# SSTuino_Evo.net
KiCad netlist of a schematic drawn in EAGLE
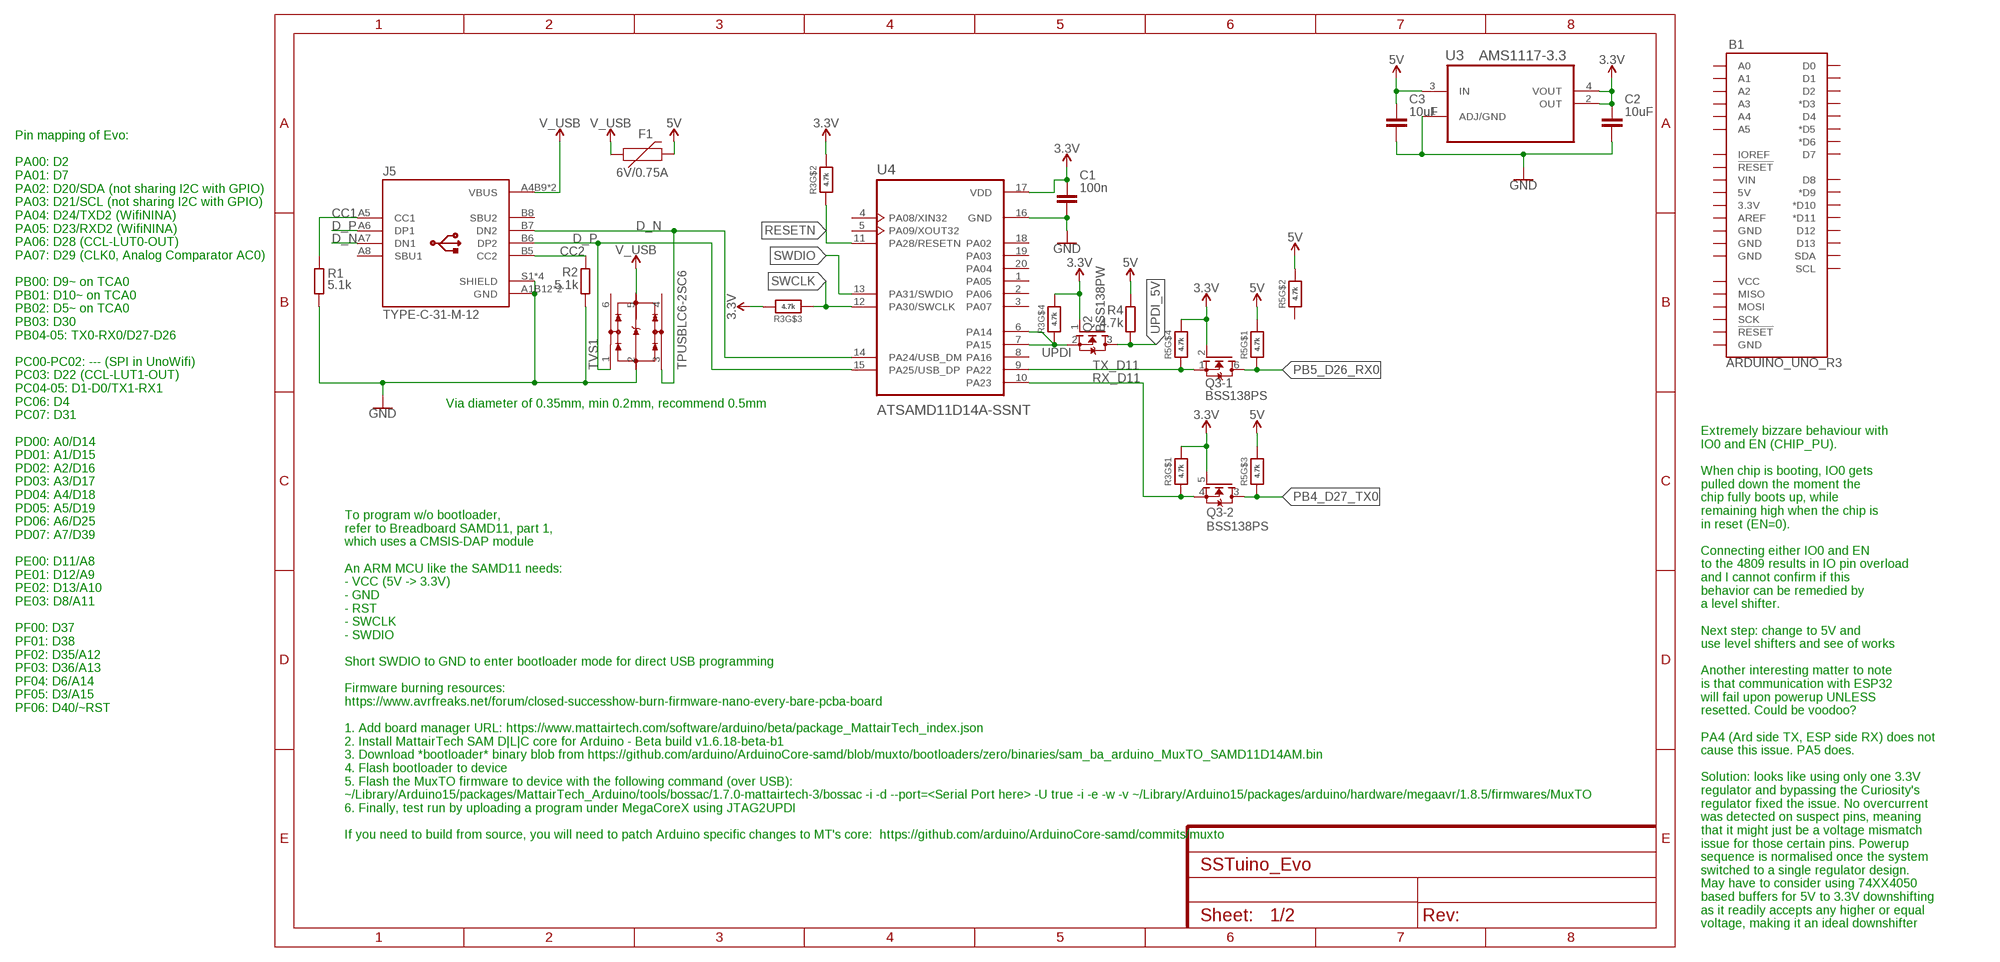
[diagram p0: schematic, sheet 1]
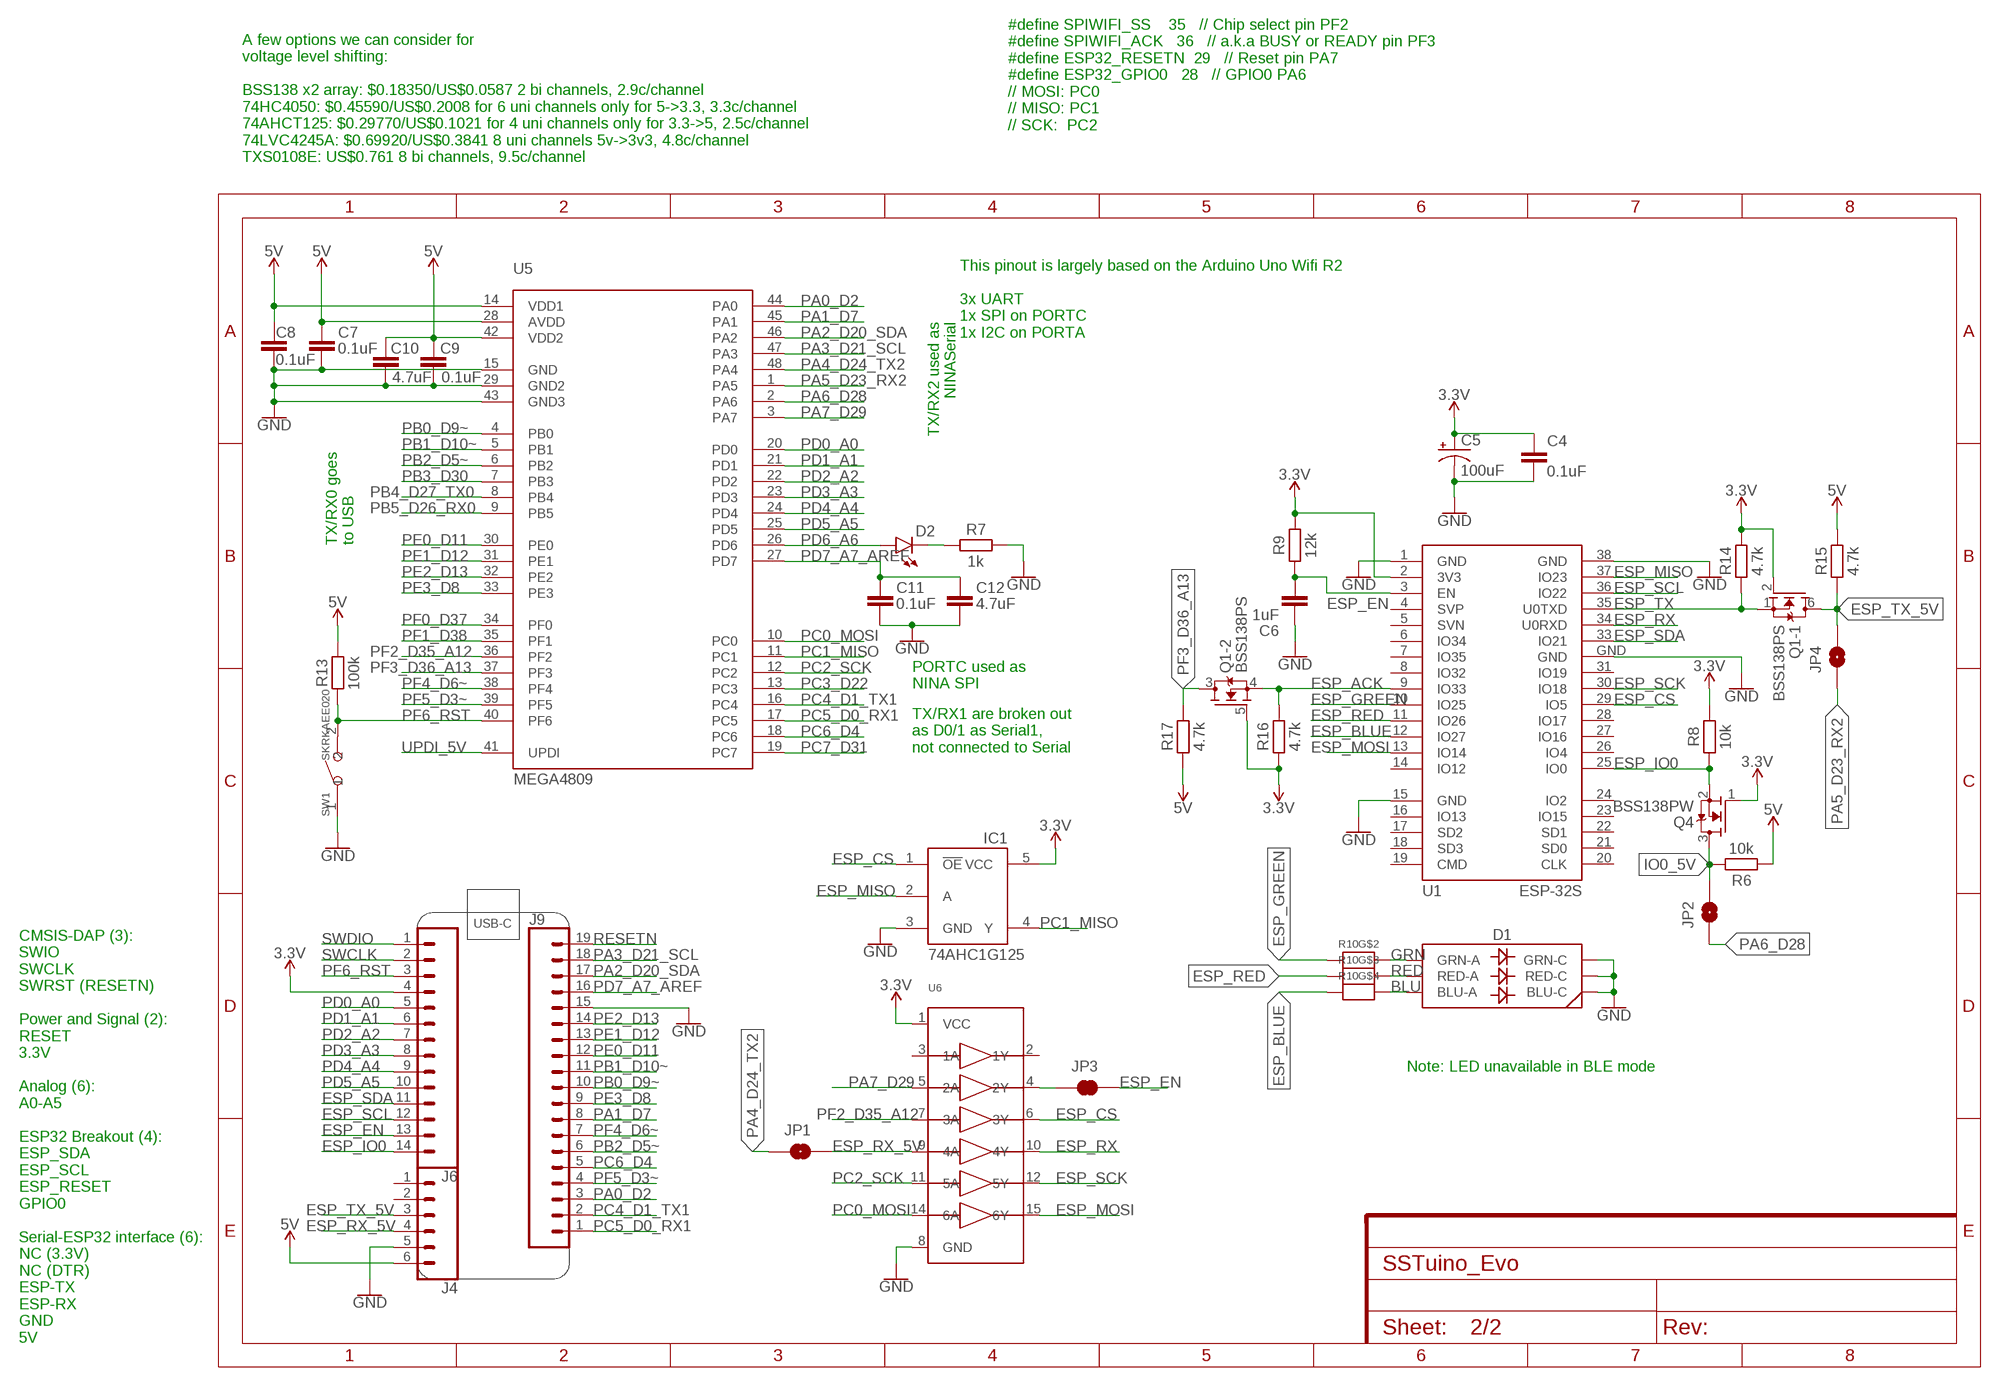
[diagram p1: schematic, sheet 2]

(export (version "E")
  (design (tool "Eeschema 10.0.6"))
  (components
    (comp (ref "C4")
      (value "0.1uF")
      (footprint "eagle-import:CAPC1005X60")
      (libsource (lib "eagle-import") (part "CCHIP-0402(1005-METRIC)_"))
    )
    (comp (ref "C5")
      (value "100uF")
      (footprint "eagle-import:CAPMP3216X180N")
      (libsource (lib "eagle-import") (part "C-POL-USTANTALUM-1206(3216-METRIC)_"))
    )
    (comp (ref "C6")
      (value "1uF")
      (footprint "eagle-import:CAPC1005X60")
      (libsource (lib "eagle-import") (part "CCHIP-0402(1005-METRIC)_"))
    )
    (comp (ref "C7")
      (value "0.1uF")
      (footprint "eagle-import:CAPC1005X60")
      (libsource (lib "eagle-import") (part "CCHIP-0402(1005-METRIC)_"))
    )
    (comp (ref "C8")
      (value "0.1uF")
      (footprint "eagle-import:CAPC1005X60")
      (libsource (lib "eagle-import") (part "CCHIP-0402(1005-METRIC)_"))
    )
    (comp (ref "C9")
      (value "0.1uF")
      (footprint "eagle-import:CAPC1005X60")
      (libsource (lib "eagle-import") (part "CCHIP-0402(1005-METRIC)_"))
    )
    (comp (ref "C10")
      (value "4.7uF")
      (footprint "eagle-import:CAPC1005X60")
      (libsource (lib "eagle-import") (part "CCHIP-0402(1005-METRIC)_"))
    )
    (comp (ref "C11")
      (value "0.1uF")
      (footprint "eagle-import:CAPC1005X60")
      (libsource (lib "eagle-import") (part "CCHIP-0402(1005-METRIC)_"))
    )
    (comp (ref "C12")
      (value "4.7uF")
      (footprint "eagle-import:CAPC1005X60")
      (libsource (lib "eagle-import") (part "CCHIP-0402(1005-METRIC)_"))
    )
    (comp (ref "D1")
      (value "LED-RGBTC5050RGBF08")
      (footprint "eagle-import:LED-TRICOLOR-5050")
      (libsource (lib "eagle-import") (part "LED-RGBTC5050RGBF08"))
    )
    (comp (ref "D2")
      (value "LED0603")
      (footprint "eagle-import:LED-0603")
      (libsource (lib "eagle-import") (part "LED0603"))
    )
    (comp (ref "IC1")
      (value "74AHC1G125")
      (footprint "eagle-import:SOT23-5L")
      (fields (field (name "LCSC_PART") "C124295"))
      (libsource (lib "eagle-import") (part "74AHC1G125"))
    )
    (comp (ref "J4")
      (value "CONN_06NO_SILK_FEMALE_PTH")
      (footprint "eagle-import:1X06_NO_SILK")
      (libsource (lib "eagle-import") (part "CONN_06NO_SILK_FEMALE_PTH"))
    )
    (comp (ref "J6")
      (value "CONN_14NO_SILK")
      (footprint "eagle-import:1X14_NO_SILK")
      (libsource (lib "eagle-import") (part "CONN_14NO_SILK"))
    )
    (comp (ref "J9")
      (value "CONN_191X19_NO_SILK")
      (footprint "eagle-import:1X19_NO_SILK")
      (libsource (lib "eagle-import") (part "CONN_191X19_NO_SILK"))
    )
    (comp (ref "JP1")
      (value "JUMPER-SMT_2_NO_SILK")
      (footprint "eagle-import:SMT-JUMPER_2_NO_SILK")
      (libsource (lib "eagle-import") (part "JUMPER-SMT_2_NO_SILK"))
    )
    (comp (ref "JP2")
      (value "JUMPER-SMT_2_NO_SILK")
      (footprint "eagle-import:SMT-JUMPER_2_NO_SILK")
      (libsource (lib "eagle-import") (part "JUMPER-SMT_2_NO_SILK"))
    )
    (comp (ref "JP3")
      (value "JUMPER-SMT_2_NC_TRACE_SILK")
      (footprint "eagle-import:SMT-JUMPER_2_NC_TRACE_SILK")
      (libsource (lib "eagle-import") (part "JUMPER-SMT_2_NC_TRACE_SILK"))
    )
    (comp (ref "JP4")
      (value "JUMPER-SMT_2_NO_SILK")
      (footprint "eagle-import:SMT-JUMPER_2_NO_SILK")
      (libsource (lib "eagle-import") (part "JUMPER-SMT_2_NO_SILK"))
    )
    (comp (ref "Q1")
      (value "BSS138PS")
      (footprint "eagle-import:ARDUINO-TRANSISTORS_SOT363")
      (fields (field (name "MANUFACTURER") "NXP") (field (name "LCSC_PART") "C193381"))
      (libsource (lib "eagle-import") (part "BSS138PS"))
    )
    (comp (ref "Q4")
      (value "BSS138PW")
      (footprint "eagle-import:SOT65P210X110-3N")
      (fields (field (name "MF") "NXP Semiconductors"))
      (libsource (lib "eagle-import") (part "BSS138PW"))
    )
    (comp (ref "R6")
      (value "10k")
      (footprint "eagle-import:RESC1005X40")
      (libsource (lib "eagle-import") (part "RCHIP-0402(1005-METRIC)_"))
    )
    (comp (ref "R7")
      (value "1k")
      (footprint "eagle-import:RESC1005X40")
      (libsource (lib "eagle-import") (part "RCHIP-0402(1005-METRIC)_"))
    )
    (comp (ref "R8")
      (value "10k")
      (footprint "eagle-import:RESC1005X40")
      (libsource (lib "eagle-import") (part "RCHIP-0402(1005-METRIC)_"))
    )
    (comp (ref "R9")
      (value "12k")
      (footprint "eagle-import:RESC1005X40")
      (libsource (lib "eagle-import") (part "RCHIP-0402(1005-METRIC)_"))
    )
    (comp (ref "R10")
      (value "RESISTOR_4PACK0402")
      (footprint "eagle-import:RESPACK_4X0402")
      (libsource (lib "eagle-import") (part "RESISTOR_4PACK0402"))
    )
    (comp (ref "R13")
      (value "100k")
      (footprint "eagle-import:RESC1005X40")
      (libsource (lib "eagle-import") (part "RCHIP-0402(1005-METRIC)_"))
    )
    (comp (ref "R14")
      (value "4.7k")
      (footprint "eagle-import:RESC1005X40")
      (libsource (lib "eagle-import") (part "RCHIP-0402(1005-METRIC)_"))
    )
    (comp (ref "R15")
      (value "4.7k")
      (footprint "eagle-import:RESC1005X40")
      (libsource (lib "eagle-import") (part "RCHIP-0402(1005-METRIC)_"))
    )
    (comp (ref "R16")
      (value "4.7k")
      (footprint "eagle-import:RESC1005X40")
      (libsource (lib "eagle-import") (part "RCHIP-0402(1005-METRIC)_"))
    )
    (comp (ref "R17")
      (value "4.7k")
      (footprint "eagle-import:RESC1005X40")
      (libsource (lib "eagle-import") (part "RCHIP-0402(1005-METRIC)_"))
    )
    (comp (ref "SW1")
      (value "SKRKAEE020")
      (footprint "eagle-import:SW2-2.6-3.9X2.9X1.5+0.4MM")
      (fields (field (name "LCSC_PART") "C115357") (field (name "LCSC_PART_1") "C115357"))
      (libsource (lib "eagle-import") (part "SMD-BUTTON(2P-3.9X2.9X1.5+0.4MM)-SKRKAEE020"))
    )
    (comp (ref "U1")
      (value "ESP-32S")
      (footprint "eagle-import:ESP-32S")
      (libsource (lib "eagle-import") (part "ESP-32S"))
    )
    (comp (ref "U5")
      (value "MEGA4809")
      (footprint "eagle-import:TQFP48")
      (fields (field (name "LCSC_PART") "C189475"))
      (libsource (lib "eagle-import") (part "MEGA4809"))
    )
    (comp (ref "U6")
      (value "74HC4050DTSSOP")
      (footprint "eagle-import:TSSOP16")
      (fields (field (name "LCSC_PART") "C352825"))
      (libsource (lib "eagle-import") (part "74HC4050DTSSOP"))
    )
    (comp (ref "B1")
      (value "ARDUINO_UNO_R3")
      (footprint "eagle-import:ARDUINO_R3")
      (libsource (lib "eagle-import") (part "ARDUINO_UNO_R3"))
    )
    (comp (ref "C1")
      (value "100n")
      (footprint "eagle-import:CAPC1005X60")
      (libsource (lib "eagle-import") (part "CCHIP-0402(1005-METRIC)_"))
    )
    (comp (ref "C2")
      (value "10uF")
      (footprint "eagle-import:CAPC1608X85")
      (libsource (lib "eagle-import") (part "CCHIP-0603(1608-METRIC)_"))
    )
    (comp (ref "C3")
      (value "10uF")
      (footprint "eagle-import:CAPC1608X85")
      (libsource (lib "eagle-import") (part "CCHIP-0603(1608-METRIC)_"))
    )
    (comp (ref "F1")
      (value "6V/0.75A")
      (footprint "eagle-import:1206")
      (fields (field (name "LCSC_PART") "C99563"))
      (libsource (lib "eagle-import") (part "PPTC_THREE-QUARTER-AMP"))
    )
    (comp (ref "J5")
      (value "TYPE-C-31-M-12")
      (footprint "eagle-import:HRO_TYPE-C-31-M-12")
      (fields (field (name "MF") "HRO Electronics Co., Ltd.") (field (name "LCSC_PART") "C165948"))
      (libsource (lib "eagle-import") (part "TYPE-C-31-M-12"))
    )
    (comp (ref "Q2")
      (value "BSS138PW")
      (footprint "eagle-import:SOT65P210X110-3N")
      (fields (field (name "MF") "NXP Semiconductors"))
      (libsource (lib "eagle-import") (part "BSS138PW"))
    )
    (comp (ref "Q3")
      (value "BSS138PS")
      (footprint "eagle-import:ARDUINO-TRANSISTORS_SOT363")
      (fields (field (name "MANUFACTURER") "NXP") (field (name "LCSC_PART") "C193381"))
      (libsource (lib "eagle-import") (part "BSS138PS"))
    )
    (comp (ref "R1")
      (value "5.1k")
      (footprint "eagle-import:RESC1005X40")
      (libsource (lib "eagle-import") (part "RCHIP-0402(1005-METRIC)_"))
    )
    (comp (ref "R2")
      (value "5.1k")
      (footprint "eagle-import:RESC1005X40")
      (libsource (lib "eagle-import") (part "RCHIP-0402(1005-METRIC)_"))
    )
    (comp (ref "R3")
      (value "4.7k")
      (footprint "eagle-import:RESPACK_4X0402")
      (fields (field (name "LCSC_PART") "C1980"))
      (libsource (lib "eagle-import") (part "RESISTOR_4PACK0402"))
    )
    (comp (ref "R4")
      (value "4.7k")
      (footprint "eagle-import:RESC1005X40")
      (libsource (lib "eagle-import") (part "RCHIP-0402(1005-METRIC)_"))
    )
    (comp (ref "R5")
      (value "4.7k")
      (footprint "eagle-import:RESPACK_4X0402")
      (fields (field (name "LCSC_PART") "C1980"))
      (libsource (lib "eagle-import") (part "RESISTOR_4PACK0402"))
    )
    (comp (ref "TVS1")
      (value "TPUSBLC6-2SC6")
      (footprint "eagle-import:SOT95P280X110-6N")
      (fields (field (name "LCSC_PART") "C558442"))
      (libsource (lib "eagle-import") (part "TPUSBLC6-2SC6"))
    )
    (comp (ref "U3")
      (value "AMS1117-3.3")
      (footprint "eagle-import:SOT230P696X180-4N")
      (fields (field (name "MPN") "LM1117MP-3.3") (field (name "LCSC_PART") "C6186"))
      (libsource (lib "eagle-import") (part "LM1117MP-3.3"))
    )
    (comp (ref "U4")
      (value "ATSAMD11D14A-SSNT")
      (footprint "eagle-import:SOIC127P1030X265-20N")
      (fields (field (name "MF") "Microchip") (field (name "LCSC_PART") "C2053599"))
      (libsource (lib "eagle-import") (part "ATSAMD11D14A-SSNT"))
    )
  )
  (nets
    (net (code "1") (name "3.3V") (class "Default")
      (node (ref "C1") (pin "1") (pinfunction "1_1") (pintype "passive"))
      (node (ref "C2") (pin "1") (pinfunction "1_1") (pintype "passive"))
      (node (ref "C4") (pin "1") (pinfunction "1_1") (pintype "passive"))
      (node (ref "C5") (pin "1") (pinfunction "+_1") (pintype "passive"))
      (node (ref "IC1") (pin "5") (pinfunction "VCC_5") (pintype "power_in"))
      (node (ref "J6") (pin "4") (pinfunction "4_4") (pintype "passive"))
      (node (ref "Q1") (pin "2") (pinfunction "G_2") (pintype "passive"))
      (node (ref "Q1") (pin "5") (pinfunction "G_5") (pintype "passive"))
      (node (ref "Q2") (pin "1") (pinfunction "G_1") (pintype "passive"))
      (node (ref "Q3") (pin "2") (pinfunction "G_2") (pintype "passive"))
      (node (ref "Q3") (pin "5") (pinfunction "G_5") (pintype "passive"))
      (node (ref "Q4") (pin "1") (pinfunction "G_1") (pintype "passive"))
      (node (ref "R14") (pin "2") (pinfunction "2_2") (pintype "passive"))
      (node (ref "R16") (pin "1") (pinfunction "1_1") (pintype "passive"))
      (node (ref "R3") (pin "5") (pinfunction "2_5") (pintype "passive"))
      (node (ref "R3") (pin "6") (pinfunction "2_6") (pintype "passive"))
      (node (ref "R3") (pin "7") (pinfunction "2_7") (pintype "passive"))
      (node (ref "R3") (pin "8") (pinfunction "2_8") (pintype "passive"))
      (node (ref "R5") (pin "5") (pinfunction "2_5") (pintype "passive"))
      (node (ref "R8") (pin "2") (pinfunction "2_2") (pintype "passive"))
      (node (ref "R9") (pin "2") (pinfunction "2_2") (pintype "passive"))
      (node (ref "U1") (pin "2") (pinfunction "3V3_2") (pintype "power_in"))
      (node (ref "U3") (pin "2") (pinfunction "OUT_2") (pintype "output"))
      (node (ref "U3") (pin "4") (pinfunction "VOUT_4") (pintype "output"))
      (node (ref "U4") (pin "17") (pinfunction "VDD_17") (pintype "power_in"))
      (node (ref "U6") (pin "1") (pinfunction "VCC_1") (pintype "bidirectional"))
    )
    (net (code "2") (name "5V") (class "Default")
      (node (ref "C10") (pin "1") (pinfunction "1_1") (pintype "passive"))
      (node (ref "C3") (pin "1") (pinfunction "1_1") (pintype "passive"))
      (node (ref "C7") (pin "1") (pinfunction "1_1") (pintype "passive"))
      (node (ref "C8") (pin "1") (pinfunction "1_1") (pintype "passive"))
      (node (ref "C9") (pin "1") (pinfunction "1_1") (pintype "passive"))
      (node (ref "F1") (pin "2") (pinfunction "2_2") (pintype "bidirectional"))
      (node (ref "J4") (pin "6") (pinfunction "6_6") (pintype "passive"))
      (node (ref "R13") (pin "2") (pinfunction "2_2") (pintype "passive"))
      (node (ref "R15") (pin "2") (pinfunction "2_2") (pintype "passive"))
      (node (ref "R17") (pin "1") (pinfunction "1_1") (pintype "passive"))
      (node (ref "R4") (pin "2") (pinfunction "2_2") (pintype "passive"))
      (node (ref "R5") (pin "6") (pinfunction "2_6") (pintype "passive"))
      (node (ref "R5") (pin "7") (pinfunction "2_7") (pintype "passive"))
      (node (ref "R5") (pin "8") (pinfunction "2_8") (pintype "passive"))
      (node (ref "R6") (pin "1") (pinfunction "1_1") (pintype "passive"))
      (node (ref "U3") (pin "3") (pinfunction "IN_3") (pintype "input"))
      (node (ref "U5") (pin "14") (pinfunction "VDD1_14") (pintype "bidirectional"))
      (node (ref "U5") (pin "28") (pinfunction "AVDD_28") (pintype "bidirectional"))
      (node (ref "U5") (pin "42") (pinfunction "VDD2_42") (pintype "bidirectional"))
    )
    (net (code "3") (name "BLU") (class "Default")
      (node (ref "D1") (pin "6") (pinfunction "BLU-A_6") (pintype "bidirectional"))
      (node (ref "R10") (pin "5") (pinfunction "2_5") (pintype "passive"))
    )
    (net (code "4") (name "CC1") (class "Default")
      (node (ref "J5") (pin "A5") (pinfunction "CC1_A5") (pintype "bidirectional"))
      (node (ref "R1") (pin "1") (pinfunction "1_1") (pintype "passive"))
    )
    (net (code "5") (name "CC2") (class "Default")
      (node (ref "J5") (pin "B5") (pinfunction "CC2_B5") (pintype "bidirectional"))
      (node (ref "R2") (pin "2") (pinfunction "2_2") (pintype "passive"))
    )
    (net (code "6") (name "D_N") (class "Default")
      (node (ref "J5") (pin "A7") (pinfunction "DN1_A7") (pintype "bidirectional"))
      (node (ref "J5") (pin "B7") (pinfunction "DN2_B7") (pintype "bidirectional"))
      (node (ref "TVS1") (pin "3") (pinfunction "IO2_3") (pintype "passive"))
      (node (ref "U4") (pin "14") (pinfunction "PA24/USB_DM_14") (pintype "bidirectional"))
    )
    (net (code "7") (name "D_P") (class "Default")
      (node (ref "J5") (pin "A6") (pinfunction "DP1_A6") (pintype "bidirectional"))
      (node (ref "J5") (pin "B6") (pinfunction "DP2_B6") (pintype "bidirectional"))
      (node (ref "TVS1") (pin "1") (pinfunction "IO1_1") (pintype "passive"))
      (node (ref "U4") (pin "15") (pinfunction "PA25/USB_DP_15") (pintype "bidirectional"))
    )
    (net (code "8") (name "ESP_ACK") (class "Default")
      (node (ref "Q1") (pin "4") (pinfunction "S_4") (pintype "passive"))
      (node (ref "R16") (pin "2") (pinfunction "2_2") (pintype "passive"))
      (node (ref "U1") (pin "9") (pinfunction "IO33_9") (pintype "bidirectional"))
    )
    (net (code "9") (name "ESP_BLUE") (class "Default")
      (node (ref "R10") (pin "4") (pinfunction "1_4") (pintype "passive"))
      (node (ref "U1") (pin "12") (pinfunction "IO27_12") (pintype "bidirectional"))
    )
    (net (code "10") (name "ESP_CS") (class "Default")
      (node (ref "IC1") (pin "1") (pinfunction "~{OE}_1") (pintype "input"))
      (node (ref "U1") (pin "29") (pinfunction "IO5_29") (pintype "bidirectional"))
      (node (ref "U6") (pin "6") (pinfunction "3Y_6") (pintype "bidirectional"))
    )
    (net (code "11") (name "ESP_EN") (class "Default")
      (node (ref "C6") (pin "2") (pinfunction "2_2") (pintype "passive"))
      (node (ref "J6") (pin "13") (pinfunction "13_13") (pintype "passive"))
      (node (ref "JP3") (pin "2") (pinfunction "2_2") (pintype "passive"))
      (node (ref "R9") (pin "1") (pinfunction "1_1") (pintype "passive"))
      (node (ref "U1") (pin "3") (pinfunction "EN_3") (pintype "input"))
    )
    (net (code "12") (name "ESP_GREEN") (class "Default")
      (node (ref "R10") (pin "2") (pinfunction "1_2") (pintype "passive"))
      (node (ref "U1") (pin "10") (pinfunction "IO25_10") (pintype "bidirectional"))
    )
    (net (code "13") (name "ESP_IO0") (class "Default")
      (node (ref "J6") (pin "14") (pinfunction "14_14") (pintype "passive"))
      (node (ref "Q4") (pin "2") (pinfunction "S_2") (pintype "passive"))
      (node (ref "R8") (pin "1") (pinfunction "1_1") (pintype "passive"))
      (node (ref "U1") (pin "25") (pinfunction "IO0_25") (pintype "bidirectional"))
    )
    (net (code "14") (name "ESP_MISO") (class "Default")
      (node (ref "IC1") (pin "2") (pinfunction "A_2") (pintype "input"))
      (node (ref "U1") (pin "37") (pinfunction "IO23_37") (pintype "bidirectional"))
    )
    (net (code "15") (name "ESP_MOSI") (class "Default")
      (node (ref "U1") (pin "13") (pinfunction "IO14_13") (pintype "bidirectional"))
      (node (ref "U6") (pin "15") (pinfunction "6Y_15") (pintype "bidirectional"))
    )
    (net (code "16") (name "ESP_RED") (class "Default")
      (node (ref "R10") (pin "3") (pinfunction "1_3") (pintype "passive"))
      (node (ref "U1") (pin "11") (pinfunction "IO26_11") (pintype "bidirectional"))
    )
    (net (code "17") (name "ESP_RX") (class "Default")
      (node (ref "U1") (pin "34") (pinfunction "U0RXD_34") (pintype "bidirectional"))
      (node (ref "U6") (pin "10") (pinfunction "4Y_10") (pintype "bidirectional"))
    )
    (net (code "18") (name "ESP_RX_5V") (class "Default")
      (node (ref "J4") (pin "4") (pinfunction "4_4") (pintype "passive"))
      (node (ref "JP1") (pin "2") (pinfunction "2_2") (pintype "passive"))
      (node (ref "U6") (pin "9") (pinfunction "4A_9") (pintype "bidirectional"))
    )
    (net (code "19") (name "ESP_SCK") (class "Default")
      (node (ref "U1") (pin "30") (pinfunction "IO18_30") (pintype "bidirectional"))
      (node (ref "U6") (pin "12") (pinfunction "5Y_12") (pintype "bidirectional"))
    )
    (net (code "20") (name "ESP_SCL") (class "Default")
      (node (ref "J6") (pin "12") (pinfunction "12_12") (pintype "passive"))
      (node (ref "U1") (pin "36") (pinfunction "IO22_36") (pintype "bidirectional"))
    )
    (net (code "21") (name "ESP_SDA") (class "Default")
      (node (ref "J6") (pin "11") (pinfunction "11_11") (pintype "passive"))
      (node (ref "U1") (pin "33") (pinfunction "IO21_33") (pintype "bidirectional"))
    )
    (net (code "22") (name "ESP_TX") (class "Default")
      (node (ref "Q1") (pin "1") (pinfunction "S_1") (pintype "passive"))
      (node (ref "R14") (pin "1") (pinfunction "1_1") (pintype "passive"))
      (node (ref "U1") (pin "35") (pinfunction "U0TXD_35") (pintype "bidirectional"))
    )
    (net (code "23") (name "ESP_TX_5V") (class "Default")
      (node (ref "J4") (pin "3") (pinfunction "3_3") (pintype "passive"))
      (node (ref "JP4") (pin "2") (pinfunction "2_2") (pintype "passive"))
      (node (ref "Q1") (pin "6") (pinfunction "D_6") (pintype "passive"))
      (node (ref "R15") (pin "1") (pinfunction "1_1") (pintype "passive"))
    )
    (net (code "24") (name "GND") (class "Default")
      (node (ref "C1") (pin "2") (pinfunction "2_2") (pintype "passive"))
      (node (ref "C10") (pin "2") (pinfunction "2_2") (pintype "passive"))
      (node (ref "C11") (pin "2") (pinfunction "2_2") (pintype "passive"))
      (node (ref "C12") (pin "2") (pinfunction "2_2") (pintype "passive"))
      (node (ref "C2") (pin "2") (pinfunction "2_2") (pintype "passive"))
      (node (ref "C3") (pin "2") (pinfunction "2_2") (pintype "passive"))
      (node (ref "C4") (pin "2") (pinfunction "2_2") (pintype "passive"))
      (node (ref "C5") (pin "2") (pinfunction "-_2") (pintype "passive"))
      (node (ref "C6") (pin "1") (pinfunction "1_1") (pintype "passive"))
      (node (ref "C7") (pin "2") (pinfunction "2_2") (pintype "passive"))
      (node (ref "C8") (pin "2") (pinfunction "2_2") (pintype "passive"))
      (node (ref "C9") (pin "2") (pinfunction "2_2") (pintype "passive"))
      (node (ref "D1") (pin "1") (pinfunction "BLU-C_1") (pintype "bidirectional"))
      (node (ref "D1") (pin "2") (pinfunction "RED-C_2") (pintype "bidirectional"))
      (node (ref "D1") (pin "3") (pinfunction "GRN-C_3") (pintype "bidirectional"))
      (node (ref "IC1") (pin "3") (pinfunction "GND_3") (pintype "power_in"))
      (node (ref "J4") (pin "5") (pinfunction "5_5") (pintype "passive"))
      (node (ref "J5") (pin "A1B12") (pinfunction "GND_A1B12") (pintype "power_in"))
      (node (ref "J5") (pin "B1A12") (pinfunction "GND_B1A12") (pintype "power_in"))
      (node (ref "J5") (pin "S1") (pinfunction "SHIELD_S1") (pintype "passive"))
      (node (ref "J5") (pin "S2") (pinfunction "SHIELD_S2") (pintype "passive"))
      (node (ref "J5") (pin "S3") (pinfunction "SHIELD_S3") (pintype "passive"))
      (node (ref "J5") (pin "S4") (pinfunction "SHIELD_S4") (pintype "passive"))
      (node (ref "J9") (pin "15") (pinfunction "15_15") (pintype "passive"))
      (node (ref "R1") (pin "2") (pinfunction "2_2") (pintype "passive"))
      (node (ref "R2") (pin "1") (pinfunction "1_1") (pintype "passive"))
      (node (ref "R7") (pin "2") (pinfunction "2_2") (pintype "passive"))
      (node (ref "SW1") (pin "1") (pinfunction "1_1") (pintype "bidirectional"))
      (node (ref "TVS1") (pin "2") (pinfunction "VSS_2") (pintype "power_in"))
      (node (ref "U1") (pin "1") (pinfunction "GND_1") (pintype "power_in"))
      (node (ref "U1") (pin "15") (pinfunction "GND_15") (pintype "power_in"))
      (node (ref "U1") (pin "38") (pinfunction "GND_38") (pintype "power_in"))
      (node (ref "U1") (pin "GND") (pinfunction "GND_GND") (pintype "power_in"))
      (node (ref "U3") (pin "1") (pinfunction "ADJ/GND_1") (pintype "passive"))
      (node (ref "U4") (pin "16") (pinfunction "GND_16") (pintype "power_in"))
      (node (ref "U5") (pin "15") (pinfunction "GND_15") (pintype "bidirectional"))
      (node (ref "U5") (pin "29") (pinfunction "GND2_29") (pintype "bidirectional"))
      (node (ref "U5") (pin "43") (pinfunction "GND3_43") (pintype "bidirectional"))
      (node (ref "U6") (pin "8") (pinfunction "GND_8") (pintype "bidirectional"))
    )
    (net (code "25") (name "GRN") (class "Default")
      (node (ref "D1") (pin "4") (pinfunction "GRN-A_4") (pintype "bidirectional"))
      (node (ref "R10") (pin "7") (pinfunction "2_7") (pintype "passive"))
    )
    (net (code "26") (name "IO0_5V") (class "Default")
      (node (ref "JP2") (pin "2") (pinfunction "2_2") (pintype "passive"))
      (node (ref "Q4") (pin "3") (pinfunction "D_3") (pintype "passive"))
      (node (ref "R6") (pin "2") (pinfunction "2_2") (pintype "passive"))
    )
    (net (code "27") (name "Net-(D2-PadC)") (class "Default")
      (node (ref "D2") (pin "C") (pinfunction "C_C") (pintype "passive"))
      (node (ref "R7") (pin "1") (pinfunction "1_1") (pintype "passive"))
    )
    (net (code "28") (name "Net-(U6-2Y)") (class "Default")
      (node (ref "JP3") (pin "1") (pinfunction "1_1") (pintype "passive"))
      (node (ref "U6") (pin "4") (pinfunction "2Y_4") (pintype "bidirectional"))
    )
    (net (code "29") (name "PA0_D2") (class "Default")
      (node (ref "J9") (pin "3") (pinfunction "3_3") (pintype "passive"))
      (node (ref "U5") (pin "44") (pinfunction "PA0_44") (pintype "bidirectional"))
    )
    (net (code "30") (name "PA1_D7") (class "Default")
      (node (ref "J9") (pin "8") (pinfunction "8_8") (pintype "passive"))
      (node (ref "U5") (pin "45") (pinfunction "PA1_45") (pintype "bidirectional"))
    )
    (net (code "31") (name "PA2_D20_SDA") (class "Default")
      (node (ref "J9") (pin "17") (pinfunction "17_17") (pintype "passive"))
      (node (ref "U5") (pin "46") (pinfunction "PA2_46") (pintype "bidirectional"))
    )
    (net (code "32") (name "PA3_D21_SCL") (class "Default")
      (node (ref "J9") (pin "18") (pinfunction "18_18") (pintype "passive"))
      (node (ref "U5") (pin "47") (pinfunction "PA3_47") (pintype "bidirectional"))
    )
    (net (code "33") (name "PA4_D24_TX2") (class "Default")
      (node (ref "JP1") (pin "1") (pinfunction "1_1") (pintype "passive"))
      (node (ref "U5") (pin "48") (pinfunction "PA4_48") (pintype "bidirectional"))
    )
    (net (code "34") (name "PA5_D23_RX2") (class "Default")
      (node (ref "JP4") (pin "1") (pinfunction "1_1") (pintype "passive"))
      (node (ref "U5") (pin "1") (pinfunction "PA5_1") (pintype "bidirectional"))
    )
    (net (code "35") (name "PA6_D28") (class "Default")
      (node (ref "JP2") (pin "1") (pinfunction "1_1") (pintype "passive"))
      (node (ref "U5") (pin "2") (pinfunction "PA6_2") (pintype "bidirectional"))
    )
    (net (code "36") (name "PA7_D29") (class "Default")
      (node (ref "U5") (pin "3") (pinfunction "PA7_3") (pintype "bidirectional"))
      (node (ref "U6") (pin "5") (pinfunction "2A_5") (pintype "bidirectional"))
    )
    (net (code "37") (name "PB0_D9~{}") (class "Default")
      (node (ref "J9") (pin "10") (pinfunction "10_10") (pintype "passive"))
      (node (ref "U5") (pin "4") (pinfunction "PB0_4") (pintype "bidirectional"))
    )
    (net (code "38") (name "PB1_D10~{}") (class "Default")
      (node (ref "J9") (pin "11") (pinfunction "11_11") (pintype "passive"))
      (node (ref "U5") (pin "5") (pinfunction "PB1_5") (pintype "bidirectional"))
    )
    (net (code "39") (name "PB2_D5~{}") (class "Default")
      (node (ref "J9") (pin "6") (pinfunction "6_6") (pintype "passive"))
      (node (ref "U5") (pin "6") (pinfunction "PB2_6") (pintype "bidirectional"))
    )
    (net (code "40") (name "PB3_D30") (class "Default")
      (node (ref "U5") (pin "7") (pinfunction "PB3_7") (pintype "bidirectional"))
    )
    (net (code "41") (name "PB4_D27_TX0") (class "Default")
      (node (ref "Q3") (pin "3") (pinfunction "D_3") (pintype "passive"))
      (node (ref "R5") (pin "3") (pinfunction "1_3") (pintype "passive"))
      (node (ref "U5") (pin "8") (pinfunction "PB4_8") (pintype "bidirectional"))
    )
    (net (code "42") (name "PB5_D26_RX0") (class "Default")
      (node (ref "Q3") (pin "6") (pinfunction "D_6") (pintype "passive"))
      (node (ref "R5") (pin "1") (pinfunction "1_1") (pintype "passive"))
      (node (ref "U5") (pin "9") (pinfunction "PB5_9") (pintype "bidirectional"))
    )
    (net (code "43") (name "PC0_MOSI") (class "Default")
      (node (ref "U5") (pin "10") (pinfunction "PC0_10") (pintype "bidirectional"))
      (node (ref "U6") (pin "14") (pinfunction "6A_14") (pintype "bidirectional"))
    )
    (net (code "44") (name "PC1_MISO") (class "Default")
      (node (ref "IC1") (pin "4") (pinfunction "Y_4") (pintype "output"))
      (node (ref "U5") (pin "11") (pinfunction "PC1_11") (pintype "bidirectional"))
    )
    (net (code "45") (name "PC2_SCK") (class "Default")
      (node (ref "U5") (pin "12") (pinfunction "PC2_12") (pintype "bidirectional"))
      (node (ref "U6") (pin "11") (pinfunction "5A_11") (pintype "bidirectional"))
    )
    (net (code "46") (name "PC3_D22") (class "Default")
      (node (ref "U5") (pin "13") (pinfunction "PC3_13") (pintype "bidirectional"))
    )
    (net (code "47") (name "PC4_D1_TX1") (class "Default")
      (node (ref "J9") (pin "2") (pinfunction "2_2") (pintype "passive"))
      (node (ref "U5") (pin "16") (pinfunction "PC4_16") (pintype "bidirectional"))
    )
    (net (code "48") (name "PC5_D0_RX1") (class "Default")
      (node (ref "J9") (pin "1") (pinfunction "1_1") (pintype "passive"))
      (node (ref "U5") (pin "17") (pinfunction "PC5_17") (pintype "bidirectional"))
    )
    (net (code "49") (name "PC6_D4") (class "Default")
      (node (ref "J9") (pin "5") (pinfunction "5_5") (pintype "passive"))
      (node (ref "U5") (pin "18") (pinfunction "PC6_18") (pintype "bidirectional"))
    )
    (net (code "50") (name "PC7_D31") (class "Default")
      (node (ref "U5") (pin "19") (pinfunction "PC7_19") (pintype "bidirectional"))
    )
    (net (code "51") (name "PD0_A0") (class "Default")
      (node (ref "J6") (pin "5") (pinfunction "5_5") (pintype "passive"))
      (node (ref "U5") (pin "20") (pinfunction "PD0_20") (pintype "bidirectional"))
    )
    (net (code "52") (name "PD1_A1") (class "Default")
      (node (ref "J6") (pin "6") (pinfunction "6_6") (pintype "passive"))
      (node (ref "U5") (pin "21") (pinfunction "PD1_21") (pintype "bidirectional"))
    )
    (net (code "53") (name "PD2_A2") (class "Default")
      (node (ref "J6") (pin "7") (pinfunction "7_7") (pintype "passive"))
      (node (ref "U5") (pin "22") (pinfunction "PD2_22") (pintype "bidirectional"))
    )
    (net (code "54") (name "PD3_A3") (class "Default")
      (node (ref "J6") (pin "8") (pinfunction "8_8") (pintype "passive"))
      (node (ref "U5") (pin "23") (pinfunction "PD3_23") (pintype "bidirectional"))
    )
    (net (code "55") (name "PD4_A4") (class "Default")
      (node (ref "J6") (pin "9") (pinfunction "9_9") (pintype "passive"))
      (node (ref "U5") (pin "24") (pinfunction "PD4_24") (pintype "bidirectional"))
    )
    (net (code "56") (name "PD5_A5") (class "Default")
      (node (ref "J6") (pin "10") (pinfunction "10_10") (pintype "passive"))
      (node (ref "U5") (pin "25") (pinfunction "PD5_25") (pintype "bidirectional"))
    )
    (net (code "57") (name "PD6_A6") (class "Default")
      (node (ref "D2") (pin "A") (pinfunction "A_A") (pintype "passive"))
      (node (ref "U5") (pin "26") (pinfunction "PD6_26") (pintype "bidirectional"))
    )
    (net (code "58") (name "PD7_A7_AREF") (class "Default")
      (node (ref "C11") (pin "1") (pinfunction "1_1") (pintype "passive"))
      (node (ref "C12") (pin "1") (pinfunction "1_1") (pintype "passive"))
      (node (ref "J9") (pin "16") (pinfunction "16_16") (pintype "passive"))
      (node (ref "U5") (pin "27") (pinfunction "PD7_27") (pintype "bidirectional"))
    )
    (net (code "59") (name "PE0_D11") (class "Default")
      (node (ref "J9") (pin "12") (pinfunction "12_12") (pintype "passive"))
      (node (ref "U5") (pin "30") (pinfunction "PE0_30") (pintype "bidirectional"))
    )
    (net (code "60") (name "PE1_D12") (class "Default")
      (node (ref "J9") (pin "13") (pinfunction "13_13") (pintype "passive"))
      (node (ref "U5") (pin "31") (pinfunction "PE1_31") (pintype "bidirectional"))
    )
    (net (code "61") (name "PE2_D13") (class "Default")
      (node (ref "J9") (pin "14") (pinfunction "14_14") (pintype "passive"))
      (node (ref "U5") (pin "32") (pinfunction "PE2_32") (pintype "bidirectional"))
    )
    (net (code "62") (name "PE3_D8") (class "Default")
      (node (ref "J9") (pin "9") (pinfunction "9_9") (pintype "passive"))
      (node (ref "U5") (pin "33") (pinfunction "PE3_33") (pintype "bidirectional"))
    )
    (net (code "63") (name "PF0_D37") (class "Default")
      (node (ref "U5") (pin "34") (pinfunction "PF0_34") (pintype "bidirectional"))
    )
    (net (code "64") (name "PF1_D38") (class "Default")
      (node (ref "U5") (pin "35") (pinfunction "PF1_35") (pintype "bidirectional"))
    )
    (net (code "65") (name "PF2_D35_A12") (class "Default")
      (node (ref "U5") (pin "36") (pinfunction "PF2_36") (pintype "bidirectional"))
      (node (ref "U6") (pin "7") (pinfunction "3A_7") (pintype "bidirectional"))
    )
    (net (code "66") (name "PF3_D36_A13") (class "Default")
      (node (ref "Q1") (pin "3") (pinfunction "D_3") (pintype "passive"))
      (node (ref "R17") (pin "2") (pinfunction "2_2") (pintype "passive"))
      (node (ref "U5") (pin "37") (pinfunction "PF3_37") (pintype "bidirectional"))
    )
    (net (code "67") (name "PF4_D6~{}") (class "Default")
      (node (ref "J9") (pin "7") (pinfunction "7_7") (pintype "passive"))
      (node (ref "U5") (pin "38") (pinfunction "PF4_38") (pintype "bidirectional"))
    )
    (net (code "68") (name "PF5_D3~{}") (class "Default")
      (node (ref "J9") (pin "4") (pinfunction "4_4") (pintype "passive"))
      (node (ref "U5") (pin "39") (pinfunction "PF5_39") (pintype "bidirectional"))
    )
    (net (code "69") (name "PF6_RST") (class "Default")
      (node (ref "J6") (pin "3") (pinfunction "3_3") (pintype "passive"))
      (node (ref "R13") (pin "1") (pinfunction "1_1") (pintype "passive"))
      (node (ref "SW1") (pin "2") (pinfunction "2_2") (pintype "bidirectional"))
      (node (ref "U5") (pin "40") (pinfunction "PF6_40") (pintype "bidirectional"))
    )
    (net (code "70") (name "RED") (class "Default")
      (node (ref "D1") (pin "5") (pinfunction "RED-A_5") (pintype "bidirectional"))
      (node (ref "R10") (pin "6") (pinfunction "2_6") (pintype "passive"))
    )
    (net (code "71") (name "RESETN") (class "Default")
      (node (ref "J9") (pin "19") (pinfunction "19_19") (pintype "passive"))
      (node (ref "R3") (pin "2") (pinfunction "1_2") (pintype "passive"))
      (node (ref "U4") (pin "11") (pinfunction "PA28/RESETN_11") (pintype "input"))
    )
    (net (code "72") (name "RX_D11") (class "Default")
      (node (ref "Q3") (pin "4") (pinfunction "S_4") (pintype "passive"))
      (node (ref "R3") (pin "1") (pinfunction "1_1") (pintype "passive"))
      (node (ref "U4") (pin "10") (pinfunction "PA23_10") (pintype "bidirectional"))
    )
    (net (code "73") (name "SWCLK") (class "Default")
      (node (ref "J6") (pin "2") (pinfunction "2_2") (pintype "passive"))
      (node (ref "R3") (pin "3") (pinfunction "1_3") (pintype "passive"))
      (node (ref "U4") (pin "12") (pinfunction "PA30/SWCLK_12") (pintype "bidirectional"))
    )
    (net (code "74") (name "SWDIO") (class "Default")
      (node (ref "J6") (pin "1") (pinfunction "1_1") (pintype "passive"))
      (node (ref "U4") (pin "13") (pinfunction "PA31/SWDIO_13") (pintype "bidirectional"))
    )
    (net (code "75") (name "TX_D11") (class "Default")
      (node (ref "Q3") (pin "1") (pinfunction "S_1") (pintype "passive"))
      (node (ref "R5") (pin "4") (pinfunction "1_4") (pintype "passive"))
      (node (ref "U4") (pin "9") (pinfunction "PA22_9") (pintype "bidirectional"))
    )
    (net (code "76") (name "UPDI") (class "Default")
      (node (ref "Q2") (pin "2") (pinfunction "S_2") (pintype "passive"))
      (node (ref "R3") (pin "4") (pinfunction "1_4") (pintype "passive"))
      (node (ref "U4") (pin "6") (pinfunction "PA14_6") (pintype "bidirectional"))
      (node (ref "U4") (pin "7") (pinfunction "PA15_7") (pintype "bidirectional"))
    )
    (net (code "77") (name "UPDI_5V") (class "Default")
      (node (ref "Q2") (pin "3") (pinfunction "D_3") (pintype "passive"))
      (node (ref "R4") (pin "1") (pinfunction "1_1") (pintype "passive"))
      (node (ref "U5") (pin "41") (pinfunction "UPDI_41") (pintype "bidirectional"))
    )
    (net (code "78") (name "V_USB") (class "Default")
      (node (ref "F1") (pin "1") (pinfunction "1_1") (pintype "bidirectional"))
      (node (ref "J5") (pin "A4B9") (pinfunction "VBUS_A4B9") (pintype "power_in"))
      (node (ref "J5") (pin "B4A9") (pinfunction "VBUS_B4A9") (pintype "power_in"))
      (node (ref "TVS1") (pin "5") (pinfunction "VCC_5") (pintype "power_in"))
    )
    (net (code "79") (name "unconnected-(B1-*D3-PadD3)") (class "Default")
      (node (ref "B1") (pin "D3") (pinfunction "*D3_D3") (pintype "bidirectional"))
    )
    (net (code "80") (name "unconnected-(B1-*D5-PadD5)") (class "Default")
      (node (ref "B1") (pin "D5") (pinfunction "*D5_D5") (pintype "bidirectional"))
    )
    (net (code "81") (name "unconnected-(B1-*D6-PadD6)") (class "Default")
      (node (ref "B1") (pin "D6") (pinfunction "*D6_D6") (pintype "bidirectional"))
    )
    (net (code "82") (name "unconnected-(B1-*D9-PadD9)") (class "Default")
      (node (ref "B1") (pin "D9") (pinfunction "*D9_D9") (pintype "bidirectional"))
    )
    (net (code "83") (name "unconnected-(B1-*D10-PadD10)") (class "Default")
      (node (ref "B1") (pin "D10") (pinfunction "*D10_D10") (pintype "bidirectional"))
    )
    (net (code "84") (name "unconnected-(B1-*D11-PadD11)") (class "Default")
      (node (ref "B1") (pin "D11") (pinfunction "*D11_D11") (pintype "bidirectional"))
    )
    (net (code "85") (name "unconnected-(B1-GND-PadGND@1)") (class "Default")
      (node (ref "B1") (pin "GND@1") (pinfunction "GND_GND@1") (pintype "bidirectional"))
    )
    (net (code "86") (name "unconnected-(B1-GND-PadGND@2)") (class "Default")
      (node (ref "B1") (pin "GND@2") (pinfunction "GND_GND@2") (pintype "bidirectional"))
    )
    (net (code "87") (name "unconnected-(B1-GND-PadGND@3)") (class "Default")
      (node (ref "B1") (pin "GND@3") (pinfunction "GND_GND@3") (pintype "bidirectional"))
    )
    (net (code "88") (name "unconnected-(B1-GND-PadGND@4)") (class "Default")
      (node (ref "B1") (pin "GND@4") (pinfunction "GND_GND@4") (pintype "bidirectional"))
    )
    (net (code "89") (name "unconnected-(B1-Pad3.3V)") (class "Default")
      (node (ref "B1") (pin "3.3V") (pinfunction "3.3V_3.3V") (pintype "bidirectional"))
    )
    (net (code "90") (name "unconnected-(B1-Pad5V)") (class "Default")
      (node (ref "B1") (pin "5V") (pinfunction "5V_5V") (pintype "bidirectional"))
    )
    (net (code "91") (name "unconnected-(B1-PadA0)") (class "Default")
      (node (ref "B1") (pin "A0") (pinfunction "A0_A0") (pintype "bidirectional"))
    )
    (net (code "92") (name "unconnected-(B1-PadA1)") (class "Default")
      (node (ref "B1") (pin "A1") (pinfunction "A1_A1") (pintype "bidirectional"))
    )
    (net (code "93") (name "unconnected-(B1-PadA2)") (class "Default")
      (node (ref "B1") (pin "A2") (pinfunction "A2_A2") (pintype "bidirectional"))
    )
    (net (code "94") (name "unconnected-(B1-PadA3)") (class "Default")
      (node (ref "B1") (pin "A3") (pinfunction "A3_A3") (pintype "bidirectional"))
    )
    (net (code "95") (name "unconnected-(B1-PadA4)") (class "Default")
      (node (ref "B1") (pin "A4") (pinfunction "A4_A4") (pintype "bidirectional"))
    )
    (net (code "96") (name "unconnected-(B1-PadA5)") (class "Default")
      (node (ref "B1") (pin "A5") (pinfunction "A5_A5") (pintype "bidirectional"))
    )
    (net (code "97") (name "unconnected-(B1-PadAREF)") (class "Default")
      (node (ref "B1") (pin "AREF") (pinfunction "AREF_AREF") (pintype "bidirectional"))
    )
    (net (code "98") (name "unconnected-(B1-PadD0)") (class "Default")
      (node (ref "B1") (pin "D0") (pinfunction "D0_D0") (pintype "bidirectional"))
    )
    (net (code "99") (name "unconnected-(B1-PadD1)") (class "Default")
      (node (ref "B1") (pin "D1") (pinfunction "D1_D1") (pintype "bidirectional"))
    )
    (net (code "100") (name "unconnected-(B1-PadD2)") (class "Default")
      (node (ref "B1") (pin "D2") (pinfunction "D2_D2") (pintype "bidirectional"))
    )
    (net (code "101") (name "unconnected-(B1-PadD4)") (class "Default")
      (node (ref "B1") (pin "D4") (pinfunction "D4_D4") (pintype "bidirectional"))
    )
    (net (code "102") (name "unconnected-(B1-PadD7)") (class "Default")
      (node (ref "B1") (pin "D7") (pinfunction "D7_D7") (pintype "bidirectional"))
    )
    (net (code "103") (name "unconnected-(B1-PadD8)") (class "Default")
      (node (ref "B1") (pin "D8") (pinfunction "D8_D8") (pintype "bidirectional"))
    )
    (net (code "104") (name "unconnected-(B1-PadD12)") (class "Default")
      (node (ref "B1") (pin "D12") (pinfunction "D12_D12") (pintype "bidirectional"))
    )
    (net (code "105") (name "unconnected-(B1-PadD13)") (class "Default")
      (node (ref "B1") (pin "D13") (pinfunction "D13_D13") (pintype "bidirectional"))
    )
    (net (code "106") (name "unconnected-(B1-PadIOREF)") (class "Default")
      (node (ref "B1") (pin "IOREF") (pinfunction "IOREF_IOREF") (pintype "bidirectional"))
    )
    (net (code "107") (name "unconnected-(B1-PadMISO)") (class "Default")
      (node (ref "B1") (pin "MISO") (pinfunction "MISO_MISO") (pintype "bidirectional"))
    )
    (net (code "108") (name "unconnected-(B1-PadMOSI)") (class "Default")
      (node (ref "B1") (pin "MOSI") (pinfunction "MOSI_MOSI") (pintype "bidirectional"))
    )
    (net (code "109") (name "unconnected-(B1-PadSCK)") (class "Default")
      (node (ref "B1") (pin "SCK") (pinfunction "SCK_SCK") (pintype "bidirectional"))
    )
    (net (code "110") (name "unconnected-(B1-PadSCL)") (class "Default")
      (node (ref "B1") (pin "SCL") (pinfunction "SCL_SCL") (pintype "bidirectional"))
    )
    (net (code "111") (name "unconnected-(B1-PadSDA)") (class "Default")
      (node (ref "B1") (pin "SDA") (pinfunction "SDA_SDA") (pintype "bidirectional"))
    )
    (net (code "112") (name "unconnected-(B1-PadVCC)") (class "Default")
      (node (ref "B1") (pin "VCC") (pinfunction "VCC_VCC") (pintype "bidirectional"))
    )
    (net (code "113") (name "unconnected-(B1-PadVIN)") (class "Default")
      (node (ref "B1") (pin "VIN") (pinfunction "VIN_VIN") (pintype "bidirectional"))
    )
    (net (code "114") (name "unconnected-(B1-~{RESET}-PadRESET@1)") (class "Default")
      (node (ref "B1") (pin "RESET@1") (pinfunction "~{RESET}_RESET@1") (pintype "bidirectional"))
    )
    (net (code "115") (name "unconnected-(B1-~{RESET}-PadRESET@2)") (class "Default")
      (node (ref "B1") (pin "RESET@2") (pinfunction "~{RESET}_RESET@2") (pintype "bidirectional"))
    )
    (net (code "116") (name "unconnected-(J4-Pad1)") (class "Default")
      (node (ref "J4") (pin "1") (pinfunction "1_1") (pintype "passive"))
    )
    (net (code "117") (name "unconnected-(J4-Pad2)") (class "Default")
      (node (ref "J4") (pin "2") (pinfunction "2_2") (pintype "passive"))
    )
    (net (code "118") (name "unconnected-(J5-SBU1-PadA8)") (class "Default")
      (node (ref "J5") (pin "A8") (pinfunction "SBU1_A8") (pintype "bidirectional"))
    )
    (net (code "119") (name "unconnected-(J5-SBU2-PadB8)") (class "Default")
      (node (ref "J5") (pin "B8") (pinfunction "SBU2_B8") (pintype "bidirectional"))
    )
    (net (code "120") (name "unconnected-(R5B-1-Pad2)") (class "Default")
      (node (ref "R5") (pin "2") (pinfunction "1_2") (pintype "passive"))
    )
    (net (code "121") (name "unconnected-(TVS1-IO3-Pad4)") (class "Default")
      (node (ref "TVS1") (pin "4") (pinfunction "IO3_4") (pintype "passive"))
    )
    (net (code "122") (name "unconnected-(TVS1-IO4-Pad6)") (class "Default")
      (node (ref "TVS1") (pin "6") (pinfunction "IO4_6") (pintype "passive"))
    )
    (net (code "123") (name "unconnected-(U1-CLK-Pad20)") (class "Default")
      (node (ref "U1") (pin "20") (pinfunction "CLK_20") (pintype "bidirectional"))
    )
    (net (code "124") (name "unconnected-(U1-CMD-Pad19)") (class "Default")
      (node (ref "U1") (pin "19") (pinfunction "CMD_19") (pintype "bidirectional"))
    )
    (net (code "125") (name "unconnected-(U1-IO2-Pad24)") (class "Default")
      (node (ref "U1") (pin "24") (pinfunction "IO2_24") (pintype "bidirectional"))
    )
    (net (code "126") (name "unconnected-(U1-IO4-Pad26)") (class "Default")
      (node (ref "U1") (pin "26") (pinfunction "IO4_26") (pintype "bidirectional"))
    )
    (net (code "127") (name "unconnected-(U1-IO12-Pad14)") (class "Default")
      (node (ref "U1") (pin "14") (pinfunction "IO12_14") (pintype "bidirectional"))
    )
    (net (code "128") (name "unconnected-(U1-IO13-Pad16)") (class "Default")
      (node (ref "U1") (pin "16") (pinfunction "IO13_16") (pintype "bidirectional"))
    )
    (net (code "129") (name "unconnected-(U1-IO15-Pad23)") (class "Default")
      (node (ref "U1") (pin "23") (pinfunction "IO15_23") (pintype "bidirectional"))
    )
    (net (code "130") (name "unconnected-(U1-IO16-Pad27)") (class "Default")
      (node (ref "U1") (pin "27") (pinfunction "IO16_27") (pintype "bidirectional"))
    )
    (net (code "131") (name "unconnected-(U1-IO17-Pad28)") (class "Default")
      (node (ref "U1") (pin "28") (pinfunction "IO17_28") (pintype "bidirectional"))
    )
    (net (code "132") (name "unconnected-(U1-IO19-Pad31)") (class "Default")
      (node (ref "U1") (pin "31") (pinfunction "IO19_31") (pintype "bidirectional"))
    )
    (net (code "133") (name "unconnected-(U1-IO32-Pad8)") (class "Default")
      (node (ref "U1") (pin "8") (pinfunction "IO32_8") (pintype "bidirectional"))
    )
    (net (code "134") (name "unconnected-(U1-IO34-Pad6)") (class "Default")
      (node (ref "U1") (pin "6") (pinfunction "IO34_6") (pintype "bidirectional"))
    )
    (net (code "135") (name "unconnected-(U1-IO35-Pad7)") (class "Default")
      (node (ref "U1") (pin "7") (pinfunction "IO35_7") (pintype "bidirectional"))
    )
    (net (code "136") (name "unconnected-(U1-SD0-Pad21)") (class "Default")
      (node (ref "U1") (pin "21") (pinfunction "SD0_21") (pintype "bidirectional"))
    )
    (net (code "137") (name "unconnected-(U1-SD1-Pad22)") (class "Default")
      (node (ref "U1") (pin "22") (pinfunction "SD1_22") (pintype "bidirectional"))
    )
    (net (code "138") (name "unconnected-(U1-SD2-Pad17)") (class "Default")
      (node (ref "U1") (pin "17") (pinfunction "SD2_17") (pintype "bidirectional"))
    )
    (net (code "139") (name "unconnected-(U1-SD3-Pad18)") (class "Default")
      (node (ref "U1") (pin "18") (pinfunction "SD3_18") (pintype "bidirectional"))
    )
    (net (code "140") (name "unconnected-(U1-SVN-Pad5)") (class "Default")
      (node (ref "U1") (pin "5") (pinfunction "SVN_5") (pintype "bidirectional"))
    )
    (net (code "141") (name "unconnected-(U1-SVP-Pad4)") (class "Default")
      (node (ref "U1") (pin "4") (pinfunction "SVP_4") (pintype "bidirectional"))
    )
    (net (code "142") (name "unconnected-(U4-PA02-Pad18)") (class "Default")
      (node (ref "U4") (pin "18") (pinfunction "PA02_18") (pintype "bidirectional"))
    )
    (net (code "143") (name "unconnected-(U4-PA03-Pad19)") (class "Default")
      (node (ref "U4") (pin "19") (pinfunction "PA03_19") (pintype "bidirectional"))
    )
    (net (code "144") (name "unconnected-(U4-PA04-Pad20)") (class "Default")
      (node (ref "U4") (pin "20") (pinfunction "PA04_20") (pintype "bidirectional"))
    )
    (net (code "145") (name "unconnected-(U4-PA05-Pad1)") (class "Default")
      (node (ref "U4") (pin "1") (pinfunction "PA05_1") (pintype "bidirectional"))
    )
    (net (code "146") (name "unconnected-(U4-PA06-Pad2)") (class "Default")
      (node (ref "U4") (pin "2") (pinfunction "PA06_2") (pintype "bidirectional"))
    )
    (net (code "147") (name "unconnected-(U4-PA07-Pad3)") (class "Default")
      (node (ref "U4") (pin "3") (pinfunction "PA07_3") (pintype "bidirectional"))
    )
    (net (code "148") (name "unconnected-(U4-PA08{slash}XIN32-Pad4)") (class "Default")
      (node (ref "U4") (pin "4") (pinfunction "PA08/XIN32_4") (pintype "input"))
    )
    (net (code "149") (name "unconnected-(U4-PA09{slash}XOUT32-Pad5)") (class "Default")
      (node (ref "U4") (pin "5") (pinfunction "PA09/XOUT32_5") (pintype "input"))
    )
    (net (code "150") (name "unconnected-(U4-PA16-Pad8)") (class "Default")
      (node (ref "U4") (pin "8") (pinfunction "PA16_8") (pintype "bidirectional"))
    )
    (net (code "151") (name "unconnected-(U6-1A-Pad3)") (class "Default")
      (node (ref "U6") (pin "3") (pinfunction "1A_3") (pintype "bidirectional"))
    )
    (net (code "152") (name "unconnected-(U6-1Y-Pad2)") (class "Default")
      (node (ref "U6") (pin "2") (pinfunction "1Y_2") (pintype "bidirectional"))
    )
  )
)
